# design.net
KiCad netlist of a schematic drawn in Altium Designer
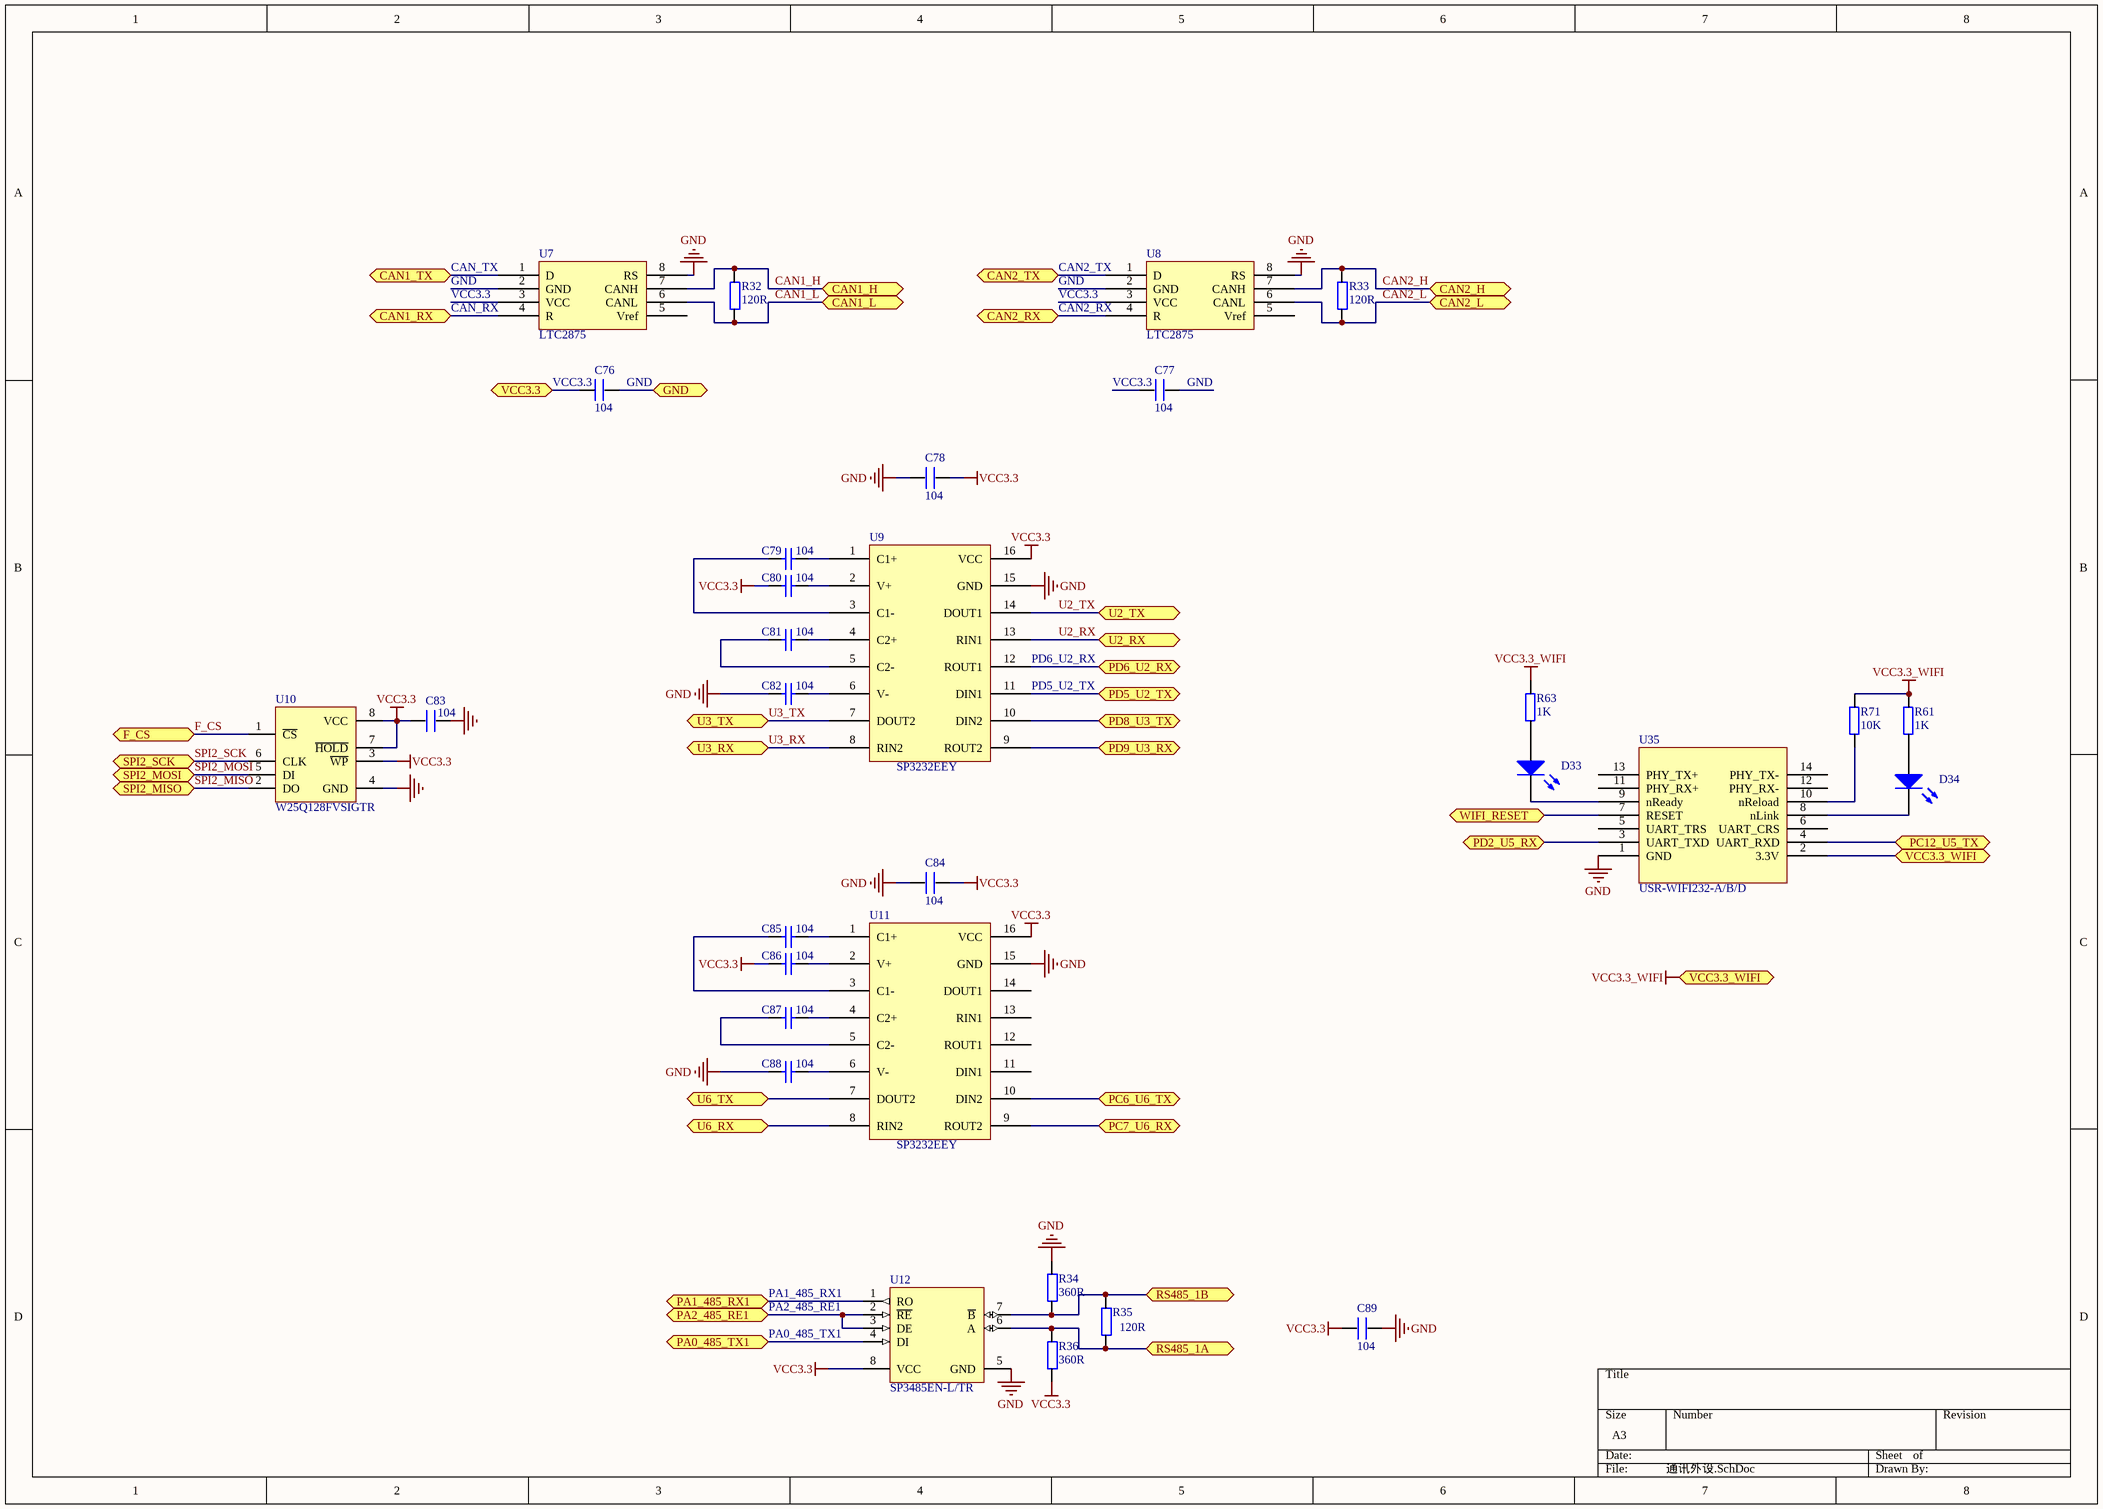
[diagram p0: 通讯外设.SchDoc]

(export (version "E")
  (design (tool "Eeschema 10.0.6"))
  (components
    (comp (ref "C76")
      (value "104")
      (footprint "0603_C")
      (libsource (lib "Explorer STM32F407封装库") (part "C_3"))
    )
    (comp (ref "C77")
      (value "104")
      (footprint "0603_C")
      (libsource (lib "Explorer STM32F407封装库") (part "C_3"))
    )
    (comp (ref "C78")
      (value "104")
      (footprint "0603_C")
      (libsource (lib "Explorer STM32F407封装库") (part "C_2"))
    )
    (comp (ref "C79")
      (value "104")
      (footprint "0603_C")
      (description "Capacitor")
      (fields (field (name "Comment") "0.1uF") (field (name "PUBLISHER") "Altium Limited"))
      (libsource (lib "Miscellaneous Devices") (part "Cap"))
    )
    (comp (ref "C80")
      (value "104")
      (footprint "0603_C")
      (description "Capacitor")
      (fields (field (name "Comment") "0.1uF") (field (name "PUBLISHER") "Altium Limited"))
      (libsource (lib "Miscellaneous Devices") (part "Cap"))
    )
    (comp (ref "C81")
      (value "104")
      (footprint "0603_C")
      (description "Capacitor")
      (fields (field (name "Comment") "0.1uF") (field (name "PUBLISHER") "Altium Limited"))
      (libsource (lib "Miscellaneous Devices") (part "Cap"))
    )
    (comp (ref "C82")
      (value "104")
      (footprint "0603_C")
      (description "Capacitor")
      (fields (field (name "Comment") "0.1uF") (field (name "PUBLISHER") "Altium Limited"))
      (libsource (lib "Miscellaneous Devices") (part "Cap"))
    )
    (comp (ref "C83") (value "104") (footprint "0603_C") (libsource (lib "WarShip V3_SCH") (part "C")))
    (comp (ref "C84")
      (value "104")
      (footprint "0603_C")
      (libsource (lib "Explorer STM32F407封装库") (part "C_2"))
    )
    (comp (ref "C85")
      (value "104")
      (footprint "0603_C")
      (description "Capacitor")
      (fields (field (name "Comment") "0.1uF") (field (name "PUBLISHER") "Altium Limited"))
      (libsource (lib "Miscellaneous Devices") (part "Cap"))
    )
    (comp (ref "C86")
      (value "104")
      (footprint "0603_C")
      (description "Capacitor")
      (fields (field (name "Comment") "0.1uF") (field (name "PUBLISHER") "Altium Limited"))
      (libsource (lib "Miscellaneous Devices") (part "Cap"))
    )
    (comp (ref "C87")
      (value "104")
      (footprint "0603_C")
      (description "Capacitor")
      (fields (field (name "Comment") "0.1uF") (field (name "PUBLISHER") "Altium Limited"))
      (libsource (lib "Miscellaneous Devices") (part "Cap"))
    )
    (comp (ref "C88")
      (value "104")
      (footprint "0603_C")
      (description "Capacitor")
      (fields (field (name "Comment") "0.1uF") (field (name "PUBLISHER") "Altium Limited"))
      (libsource (lib "Miscellaneous Devices") (part "Cap"))
    )
    (comp (ref "C89")
      (value "104")
      (footprint "0603_C")
      (libsource (lib "Explorer STM32F407封装库") (part "C_3"))
    )
    (comp (ref "D33")
      (value "红灯 0805")
      (footprint "LC-0805_LED_S1")
      (description "Typical INFRARED GaAs LED")
      (fields (field (name "PUBLISHER") "Altium Limited"))
      (libsource (lib "继电器板_1") (part "LED0"))
    )
    (comp (ref "D34")
      (value "红灯 0805")
      (footprint "LC-0805_LED_S1")
      (description "Typical INFRARED GaAs LED")
      (fields (field (name "PUBLISHER") "Altium Limited"))
      (libsource (lib "继电器板_1") (part "LED0"))
    )
    (comp (ref "R32")
      (value "120R")
      (footprint "0603_R")
      (libsource (lib "Explorer STM32F407封装库") (part "R_2"))
    )
    (comp (ref "R33")
      (value "120R")
      (footprint "0603_R")
      (libsource (lib "Explorer STM32F407封装库") (part "R_2"))
    )
    (comp (ref "R34")
      (value "360R")
      (footprint "0603_R")
      (libsource (lib "Explorer STM32F407封装库") (part "R_2"))
    )
    (comp (ref "R35")
      (value "120R")
      (footprint "0603_R")
      (libsource (lib "Explorer STM32F407封装库") (part "R_2"))
    )
    (comp (ref "R36")
      (value "360R")
      (footprint "0603_R")
      (libsource (lib "Explorer STM32F407封装库") (part "R_2"))
    )
    (comp (ref "R61")
      (value "1K")
      (footprint "0603_R")
      (libsource (lib "Explorer STM32F407封装库") (part "R_2"))
    )
    (comp (ref "R63")
      (value "1K")
      (footprint "0603_R")
      (libsource (lib "Explorer STM32F407封装库") (part "R_2"))
    )
    (comp (ref "R71")
      (value "10K")
      (footprint "0603_R")
      (libsource (lib "Explorer STM32F407封装库") (part "R_2"))
    )
    (comp (ref "U7")
      (value "LTC2875")
      (footprint "SOIC-8_150mil")
      (description "CAN")
      (libsource (lib "Miscellaneous Devices LC") (part "CAN/SN65HVD230DR"))
    )
    (comp (ref "U8")
      (value "LTC2875")
      (footprint "SOIC-8_150mil")
      (description "CAN")
      (libsource (lib "Miscellaneous Devices LC") (part "CAN/SN65HVD230DR"))
    )
    (comp (ref "U9")
      (value "SP3232EEY")
      (footprint "TSSOP-16")
      (description "RS232")
      (libsource (lib "Smart_board_v1") (part "MAX3232CUE"))
    )
    (comp (ref "U10")
      (value "W25Q128FVSIGTR")
      (footprint "SOIC8_W")
      (description "Flash ROM")
      (libsource (lib "fszhang") (part "W25QXX"))
    )
    (comp (ref "U11")
      (value "SP3232EEY")
      (footprint "TSSOP-16")
      (description "RS232")
      (libsource (lib "Smart_board_v1") (part "MAX3232CUE"))
    )
    (comp (ref "U12")
      (value "SP3485EN-L/TR")
      (footprint "SOIC-8_150mil")
      (description "RS-485/RS-422")
      (libsource (lib "Miscellaneous Devices LC") (part "SP3485EN-L/TR"))
    )
    (comp (ref "U35")
      (value "USR-WIFI232-A/B/D")
      (footprint "USR-WIFI232-A/B/D")
      (libsource (lib "USR-WIFI232-ABD-SCH") (part "USR-WIFI232-A/B/D"))
    )
  )
  (nets
    (net (code "1") (name "/CAN1_H") (class "Default")
      (node (ref "R32") (pin "2") (pintype "passive"))
      (node (ref "U7") (pin "7") (pinfunction "CANH_7") (pintype "passive"))
    )
    (net (code "2") (name "/CAN1_L") (class "Default")
      (node (ref "R32") (pin "1") (pintype "passive"))
      (node (ref "U7") (pin "6") (pinfunction "CANL_6") (pintype "passive"))
    )
    (net (code "3") (name "/CAN2_H") (class "Default")
      (node (ref "R33") (pin "2") (pintype "passive"))
      (node (ref "U8") (pin "7") (pinfunction "CANH_7") (pintype "passive"))
    )
    (net (code "4") (name "/CAN2_L") (class "Default")
      (node (ref "R33") (pin "1") (pintype "passive"))
      (node (ref "U8") (pin "6") (pinfunction "CANL_6") (pintype "passive"))
    )
    (net (code "5") (name "/CAN2_RX") (class "Default")
      (node (ref "U8") (pin "4") (pinfunction "R_4") (pintype "passive"))
    )
    (net (code "6") (name "/CAN2_TX") (class "Default")
      (node (ref "U8") (pin "1") (pinfunction "D_1") (pintype "passive"))
    )
    (net (code "7") (name "/CAN_RX") (class "Default")
      (node (ref "U7") (pin "4") (pinfunction "R_4") (pintype "passive"))
    )
    (net (code "8") (name "/CAN_TX") (class "Default")
      (node (ref "U7") (pin "1") (pinfunction "D_1") (pintype "passive"))
    )
    (net (code "9") (name "/F_CS") (class "Default")
      (node (ref "U10") (pin "1") (pinfunction "~{CS}_1") (pintype "passive"))
    )
    (net (code "10") (name "/PA0_485_TX1") (class "Default")
      (node (ref "U12") (pin "4") (pinfunction "DI_4") (pintype "input"))
    )
    (net (code "11") (name "/PA1_485_RX1") (class "Default")
      (node (ref "U12") (pin "1") (pinfunction "RO_1") (pintype "output"))
    )
    (net (code "12") (name "/PA2_485_RE1") (class "Default")
      (node (ref "U12") (pin "2") (pinfunction "~{RE}_2") (pintype "input"))
      (node (ref "U12") (pin "3") (pinfunction "DE_3") (pintype "input"))
    )
    (net (code "13") (name "/PC6_U6_TX") (class "Default")
      (node (ref "U11") (pin "10") (pinfunction "DIN2_10") (pintype "passive"))
    )
    (net (code "14") (name "/PC7_U6_RX") (class "Default")
      (node (ref "U11") (pin "9") (pinfunction "ROUT2_9") (pintype "passive"))
    )
    (net (code "15") (name "/PC12_U5_TX") (class "Default")
      (node (ref "U35") (pin "4") (pinfunction "UART_RXD_4") (pintype "passive"))
    )
    (net (code "16") (name "/PD2_U5_RX") (class "Default")
      (node (ref "U35") (pin "3") (pinfunction "UART_TXD_3") (pintype "passive"))
    )
    (net (code "17") (name "/PD5_U2_TX") (class "Default")
      (node (ref "U9") (pin "11") (pinfunction "DIN1_11") (pintype "passive"))
    )
    (net (code "18") (name "/PD6_U2_RX") (class "Default")
      (node (ref "U9") (pin "12") (pinfunction "ROUT1_12") (pintype "passive"))
    )
    (net (code "19") (name "/PD8_U3_TX") (class "Default")
      (node (ref "U9") (pin "10") (pinfunction "DIN2_10") (pintype "passive"))
    )
    (net (code "20") (name "/PD9_U3_RX") (class "Default")
      (node (ref "U9") (pin "9") (pinfunction "ROUT2_9") (pintype "passive"))
    )
    (net (code "21") (name "/RS485_1A") (class "Default")
      (node (ref "R35") (pin "1") (pintype "passive"))
      (node (ref "R36") (pin "2") (pintype "passive"))
      (node (ref "U12") (pin "6") (pinfunction "A_6") (pintype "bidirectional"))
    )
    (net (code "22") (name "/RS485_1B") (class "Default")
      (node (ref "R34") (pin "1") (pintype "passive"))
      (node (ref "R35") (pin "2") (pintype "passive"))
      (node (ref "U12") (pin "7") (pinfunction "~{B}_7") (pintype "bidirectional"))
    )
    (net (code "23") (name "/SPI2_MISO") (class "Default")
      (node (ref "U10") (pin "2") (pinfunction "DO_2") (pintype "passive"))
    )
    (net (code "24") (name "/SPI2_MOSI") (class "Default")
      (node (ref "U10") (pin "5") (pinfunction "DI_5") (pintype "passive"))
    )
    (net (code "25") (name "/SPI2_SCK") (class "Default")
      (node (ref "U10") (pin "6") (pinfunction "CLK_6") (pintype "passive"))
    )
    (net (code "26") (name "/U2_RX") (class "Default")
      (node (ref "U9") (pin "13") (pinfunction "RIN1_13") (pintype "passive"))
    )
    (net (code "27") (name "/U2_TX") (class "Default")
      (node (ref "U9") (pin "14") (pinfunction "DOUT1_14") (pintype "passive"))
    )
    (net (code "28") (name "/U3_RX") (class "Default")
      (node (ref "U9") (pin "8") (pinfunction "RIN2_8") (pintype "passive"))
    )
    (net (code "29") (name "/U3_TX") (class "Default")
      (node (ref "U9") (pin "7") (pinfunction "DOUT2_7") (pintype "passive"))
    )
    (net (code "30") (name "/U6_RX") (class "Default")
      (node (ref "U11") (pin "8") (pinfunction "RIN2_8") (pintype "passive"))
    )
    (net (code "31") (name "/U6_TX") (class "Default")
      (node (ref "U11") (pin "7") (pinfunction "DOUT2_7") (pintype "passive"))
    )
    (net (code "32") (name "/WIFI_RESET") (class "Default")
      (node (ref "U35") (pin "7") (pinfunction "RESET_7") (pintype "passive"))
    )
    (net (code "33") (name "GND") (class "Default")
      (node (ref "C76") (pin "2") (pintype "passive"))
      (node (ref "C77") (pin "2") (pintype "passive"))
      (node (ref "C78") (pin "1") (pintype "passive"))
      (node (ref "C82") (pin "2") (pinfunction "2_2") (pintype "passive"))
      (node (ref "C83") (pin "2") (pintype "passive"))
      (node (ref "C84") (pin "1") (pintype "passive"))
      (node (ref "C88") (pin "2") (pinfunction "2_2") (pintype "passive"))
      (node (ref "C89") (pin "2") (pintype "passive"))
      (node (ref "R34") (pin "2") (pintype "passive"))
      (node (ref "U10") (pin "4") (pinfunction "GND_4") (pintype "passive"))
      (node (ref "U11") (pin "15") (pinfunction "GND_15") (pintype "passive"))
      (node (ref "U12") (pin "5") (pinfunction "GND_5") (pintype "power_in"))
      (node (ref "U35") (pin "1") (pinfunction "GND_1") (pintype "passive"))
      (node (ref "U7") (pin "2") (pinfunction "GND_2") (pintype "passive"))
      (node (ref "U7") (pin "8") (pinfunction "RS_8") (pintype "passive"))
      (node (ref "U8") (pin "2") (pinfunction "GND_2") (pintype "passive"))
      (node (ref "U8") (pin "8") (pinfunction "RS_8") (pintype "passive"))
      (node (ref "U9") (pin "15") (pinfunction "GND_15") (pintype "passive"))
    )
    (net (code "34") (name "Net-(D33-PadA)") (class "Default")
      (node (ref "D33") (pin "A") (pinfunction "A_A") (pintype "passive"))
      (node (ref "R63") (pin "2") (pintype "passive"))
    )
    (net (code "35") (name "Net-(D34-PadA)") (class "Default")
      (node (ref "D34") (pin "A") (pinfunction "A_A") (pintype "passive"))
      (node (ref "R61") (pin "2") (pintype "passive"))
    )
    (net (code "36") (name "Net-(U9-C1+)") (class "Default")
      (node (ref "C79") (pin "1") (pinfunction "1_1") (pintype "passive"))
      (node (ref "U9") (pin "1") (pinfunction "C1+_1") (pintype "passive"))
    )
    (net (code "37") (name "Net-(U9-C1-)") (class "Default")
      (node (ref "C79") (pin "2") (pinfunction "2_2") (pintype "passive"))
      (node (ref "U9") (pin "3") (pinfunction "C1-_3") (pintype "passive"))
    )
    (net (code "38") (name "Net-(U9-C2+)") (class "Default")
      (node (ref "C81") (pin "1") (pinfunction "1_1") (pintype "passive"))
      (node (ref "U9") (pin "4") (pinfunction "C2+_4") (pintype "passive"))
    )
    (net (code "39") (name "Net-(U9-C2-)") (class "Default")
      (node (ref "C81") (pin "2") (pinfunction "2_2") (pintype "passive"))
      (node (ref "U9") (pin "5") (pinfunction "C2-_5") (pintype "passive"))
    )
    (net (code "40") (name "Net-(U9-V+)") (class "Default")
      (node (ref "C80") (pin "1") (pinfunction "1_1") (pintype "passive"))
      (node (ref "U9") (pin "2") (pinfunction "V+_2") (pintype "passive"))
    )
    (net (code "41") (name "Net-(U9-V-)") (class "Default")
      (node (ref "C82") (pin "1") (pinfunction "1_1") (pintype "passive"))
      (node (ref "U9") (pin "6") (pinfunction "V-_6") (pintype "passive"))
    )
    (net (code "42") (name "Net-(U11-C1+)") (class "Default")
      (node (ref "C85") (pin "1") (pinfunction "1_1") (pintype "passive"))
      (node (ref "U11") (pin "1") (pinfunction "C1+_1") (pintype "passive"))
    )
    (net (code "43") (name "Net-(U11-C1-)") (class "Default")
      (node (ref "C85") (pin "2") (pinfunction "2_2") (pintype "passive"))
      (node (ref "U11") (pin "3") (pinfunction "C1-_3") (pintype "passive"))
    )
    (net (code "44") (name "Net-(U11-C2+)") (class "Default")
      (node (ref "C87") (pin "1") (pinfunction "1_1") (pintype "passive"))
      (node (ref "U11") (pin "4") (pinfunction "C2+_4") (pintype "passive"))
    )
    (net (code "45") (name "Net-(U11-C2-)") (class "Default")
      (node (ref "C87") (pin "2") (pinfunction "2_2") (pintype "passive"))
      (node (ref "U11") (pin "5") (pinfunction "C2-_5") (pintype "passive"))
    )
    (net (code "46") (name "Net-(U11-V+)") (class "Default")
      (node (ref "C86") (pin "1") (pinfunction "1_1") (pintype "passive"))
      (node (ref "U11") (pin "2") (pinfunction "V+_2") (pintype "passive"))
    )
    (net (code "47") (name "Net-(U11-V-)") (class "Default")
      (node (ref "C88") (pin "1") (pinfunction "1_1") (pintype "passive"))
      (node (ref "U11") (pin "6") (pinfunction "V-_6") (pintype "passive"))
    )
    (net (code "48") (name "Net-(U35-nLink)") (class "Default")
      (node (ref "D34") (pin "K") (pinfunction "K_K") (pintype "passive"))
      (node (ref "U35") (pin "8") (pinfunction "nLink_8") (pintype "passive"))
    )
    (net (code "49") (name "Net-(U35-nReady)") (class "Default")
      (node (ref "D33") (pin "K") (pinfunction "K_K") (pintype "passive"))
      (node (ref "U35") (pin "9") (pinfunction "nReady_9") (pintype "passive"))
    )
    (net (code "50") (name "Net-(U35-nReload)") (class "Default")
      (node (ref "R71") (pin "2") (pintype "passive"))
      (node (ref "U35") (pin "10") (pinfunction "nReload_10") (pintype "passive"))
    )
    (net (code "51") (name "VCC3.3") (class "Default")
      (node (ref "C76") (pin "1") (pintype "passive"))
      (node (ref "C77") (pin "1") (pintype "passive"))
      (node (ref "C78") (pin "2") (pintype "passive"))
      (node (ref "C80") (pin "2") (pinfunction "2_2") (pintype "passive"))
      (node (ref "C83") (pin "1") (pintype "passive"))
      (node (ref "C84") (pin "2") (pintype "passive"))
      (node (ref "C86") (pin "2") (pinfunction "2_2") (pintype "passive"))
      (node (ref "C89") (pin "1") (pintype "passive"))
      (node (ref "R36") (pin "1") (pintype "passive"))
      (node (ref "U10") (pin "3") (pinfunction "~{WP}_3") (pintype "passive"))
      (node (ref "U10") (pin "7") (pinfunction "~{HOLD}_7") (pintype "passive"))
      (node (ref "U10") (pin "8") (pinfunction "VCC_8") (pintype "passive"))
      (node (ref "U11") (pin "16") (pinfunction "VCC_16") (pintype "passive"))
      (node (ref "U12") (pin "8") (pinfunction "VCC_8") (pintype "power_in"))
      (node (ref "U7") (pin "3") (pinfunction "VCC_3") (pintype "passive"))
      (node (ref "U8") (pin "3") (pinfunction "VCC_3") (pintype "passive"))
      (node (ref "U9") (pin "16") (pinfunction "VCC_16") (pintype "passive"))
    )
    (net (code "52") (name "VCC3.3_WIFI") (class "Default")
      (node (ref "R61") (pin "1") (pintype "passive"))
      (node (ref "R63") (pin "1") (pintype "passive"))
      (node (ref "R71") (pin "1") (pintype "passive"))
      (node (ref "U35") (pin "2") (pinfunction "3.3V_2") (pintype "passive"))
    )
    (net (code "53") (name "unconnected-(U7-Vref-Pad5)") (class "Default")
      (node (ref "U7") (pin "5") (pinfunction "Vref_5") (pintype "passive"))
    )
    (net (code "54") (name "unconnected-(U8-Vref-Pad5)") (class "Default")
      (node (ref "U8") (pin "5") (pinfunction "Vref_5") (pintype "passive"))
    )
    (net (code "55") (name "unconnected-(U11-DIN1-Pad11)") (class "Default")
      (node (ref "U11") (pin "11") (pinfunction "DIN1_11") (pintype "passive"))
    )
    (net (code "56") (name "unconnected-(U11-DOUT1-Pad14)") (class "Default")
      (node (ref "U11") (pin "14") (pinfunction "DOUT1_14") (pintype "passive"))
    )
    (net (code "57") (name "unconnected-(U11-RIN1-Pad13)") (class "Default")
      (node (ref "U11") (pin "13") (pinfunction "RIN1_13") (pintype "passive"))
    )
    (net (code "58") (name "unconnected-(U11-ROUT1-Pad12)") (class "Default")
      (node (ref "U11") (pin "12") (pinfunction "ROUT1_12") (pintype "passive"))
    )
    (net (code "59") (name "unconnected-(U35-PHY_RX+-Pad11)") (class "Default")
      (node (ref "U35") (pin "11") (pinfunction "PHY_RX+_11") (pintype "passive"))
    )
    (net (code "60") (name "unconnected-(U35-PHY_RX--Pad12)") (class "Default")
      (node (ref "U35") (pin "12") (pinfunction "PHY_RX-_12") (pintype "passive"))
    )
    (net (code "61") (name "unconnected-(U35-PHY_TX+-Pad13)") (class "Default")
      (node (ref "U35") (pin "13") (pinfunction "PHY_TX+_13") (pintype "passive"))
    )
    (net (code "62") (name "unconnected-(U35-PHY_TX--Pad14)") (class "Default")
      (node (ref "U35") (pin "14") (pinfunction "PHY_TX-_14") (pintype "passive"))
    )
    (net (code "63") (name "unconnected-(U35-UART_CRS-Pad6)") (class "Default")
      (node (ref "U35") (pin "6") (pinfunction "UART_CRS_6") (pintype "passive"))
    )
    (net (code "64") (name "unconnected-(U35-UART_TRS-Pad5)") (class "Default")
      (node (ref "U35") (pin "5") (pinfunction "UART_TRS_5") (pintype "passive"))
    )
  )
)
